# WS2803_7segs_discrete.net
KiCad netlist of a schematic drawn in EAGLE
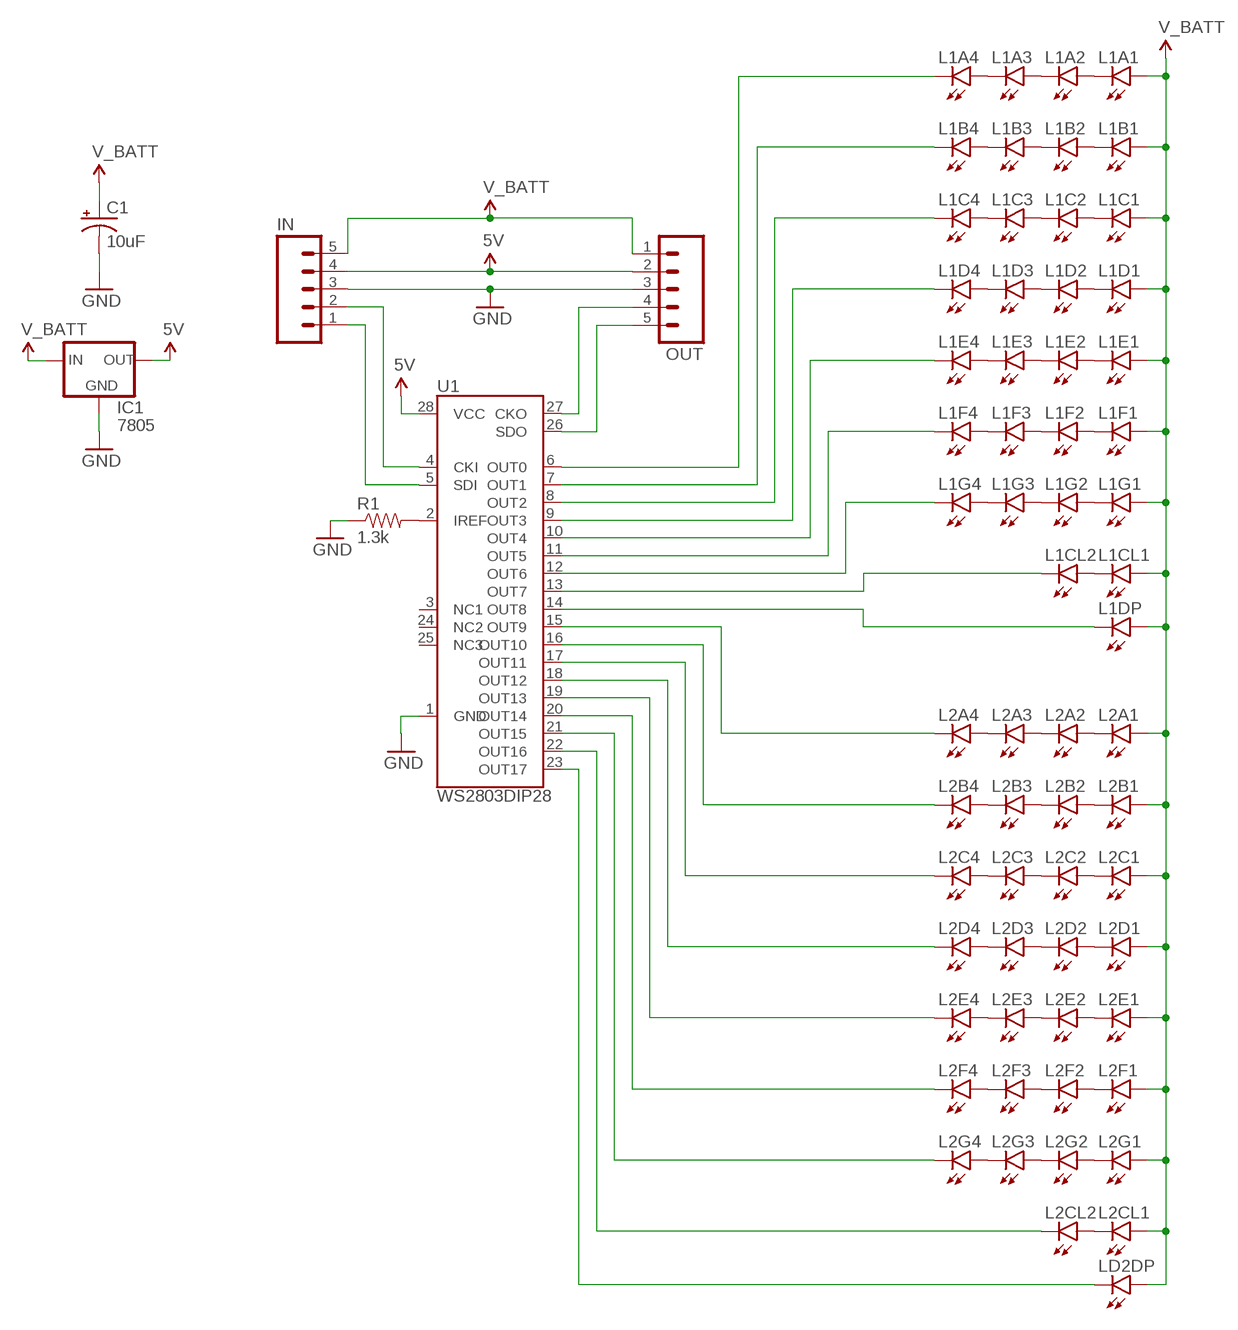
[diagram p0: schematic, sheet 1]

(export (version "E")
  (design (tool "Eeschema 10.0.6"))
  (components
    (comp (ref "C1")
      (value "10uF")
      (footprint "eagle-import:CPOL-RADIAL-10UF-25V")
      (libsource (lib "eagle-import") (part "CAP_POLPTH2"))
    )
    (comp (ref "IC1")
      (value "7805")
      (footprint "eagle-import:TO-92")
      (libsource (lib "eagle-import") (part "V_REG_78XXTO-92_FIXED"))
    )
    (comp (ref "IN")
      (value "M05PTH")
      (footprint "eagle-import:1X05")
      (libsource (lib "eagle-import") (part "M05PTH"))
    )
    (comp (ref "L1A1")
      (value "LED5MM")
      (footprint "eagle-import:LED5MM")
      (libsource (lib "eagle-import") (part "LED5MM"))
    )
    (comp (ref "L1A2")
      (value "LED5MM")
      (footprint "eagle-import:LED5MM")
      (libsource (lib "eagle-import") (part "LED5MM"))
    )
    (comp (ref "L1A3")
      (value "LED5MM")
      (footprint "eagle-import:LED5MM")
      (libsource (lib "eagle-import") (part "LED5MM"))
    )
    (comp (ref "L1A4")
      (value "LED5MM")
      (footprint "eagle-import:LED5MM")
      (libsource (lib "eagle-import") (part "LED5MM"))
    )
    (comp (ref "L1B1")
      (value "LED5MM")
      (footprint "eagle-import:LED5MM")
      (libsource (lib "eagle-import") (part "LED5MM"))
    )
    (comp (ref "L1B2")
      (value "LED5MM")
      (footprint "eagle-import:LED5MM")
      (libsource (lib "eagle-import") (part "LED5MM"))
    )
    (comp (ref "L1B3")
      (value "LED5MM")
      (footprint "eagle-import:LED5MM")
      (libsource (lib "eagle-import") (part "LED5MM"))
    )
    (comp (ref "L1B4")
      (value "LED5MM")
      (footprint "eagle-import:LED5MM")
      (libsource (lib "eagle-import") (part "LED5MM"))
    )
    (comp (ref "L1C1")
      (value "LED5MM")
      (footprint "eagle-import:LED5MM")
      (libsource (lib "eagle-import") (part "LED5MM"))
    )
    (comp (ref "L1C2")
      (value "LED5MM")
      (footprint "eagle-import:LED5MM")
      (libsource (lib "eagle-import") (part "LED5MM"))
    )
    (comp (ref "L1C3")
      (value "LED5MM")
      (footprint "eagle-import:LED5MM")
      (libsource (lib "eagle-import") (part "LED5MM"))
    )
    (comp (ref "L1C4")
      (value "LED5MM")
      (footprint "eagle-import:LED5MM")
      (libsource (lib "eagle-import") (part "LED5MM"))
    )
    (comp (ref "L1CL1")
      (value "LED5MM")
      (footprint "eagle-import:LED5MM")
      (libsource (lib "eagle-import") (part "LED5MM"))
    )
    (comp (ref "L1CL2")
      (value "LED5MM")
      (footprint "eagle-import:LED5MM")
      (libsource (lib "eagle-import") (part "LED5MM"))
    )
    (comp (ref "L1D1")
      (value "LED5MM")
      (footprint "eagle-import:LED5MM")
      (libsource (lib "eagle-import") (part "LED5MM"))
    )
    (comp (ref "L1D2")
      (value "LED5MM")
      (footprint "eagle-import:LED5MM")
      (libsource (lib "eagle-import") (part "LED5MM"))
    )
    (comp (ref "L1D3")
      (value "LED5MM")
      (footprint "eagle-import:LED5MM")
      (libsource (lib "eagle-import") (part "LED5MM"))
    )
    (comp (ref "L1D4")
      (value "LED5MM")
      (footprint "eagle-import:LED5MM")
      (libsource (lib "eagle-import") (part "LED5MM"))
    )
    (comp (ref "L1DP")
      (value "LED5MM")
      (footprint "eagle-import:LED5MM")
      (libsource (lib "eagle-import") (part "LED5MM"))
    )
    (comp (ref "L1E1")
      (value "LED5MM")
      (footprint "eagle-import:LED5MM")
      (libsource (lib "eagle-import") (part "LED5MM"))
    )
    (comp (ref "L1E2")
      (value "LED5MM")
      (footprint "eagle-import:LED5MM")
      (libsource (lib "eagle-import") (part "LED5MM"))
    )
    (comp (ref "L1E3")
      (value "LED5MM")
      (footprint "eagle-import:LED5MM")
      (libsource (lib "eagle-import") (part "LED5MM"))
    )
    (comp (ref "L1E4")
      (value "LED5MM")
      (footprint "eagle-import:LED5MM")
      (libsource (lib "eagle-import") (part "LED5MM"))
    )
    (comp (ref "L1F1")
      (value "LED5MM")
      (footprint "eagle-import:LED5MM")
      (libsource (lib "eagle-import") (part "LED5MM"))
    )
    (comp (ref "L1F2")
      (value "LED5MM")
      (footprint "eagle-import:LED5MM")
      (libsource (lib "eagle-import") (part "LED5MM"))
    )
    (comp (ref "L1F3")
      (value "LED5MM")
      (footprint "eagle-import:LED5MM")
      (libsource (lib "eagle-import") (part "LED5MM"))
    )
    (comp (ref "L1F4")
      (value "LED5MM")
      (footprint "eagle-import:LED5MM")
      (libsource (lib "eagle-import") (part "LED5MM"))
    )
    (comp (ref "L1G1")
      (value "LED5MM")
      (footprint "eagle-import:LED5MM")
      (libsource (lib "eagle-import") (part "LED5MM"))
    )
    (comp (ref "L1G2")
      (value "LED5MM")
      (footprint "eagle-import:LED5MM")
      (libsource (lib "eagle-import") (part "LED5MM"))
    )
    (comp (ref "L1G3")
      (value "LED5MM")
      (footprint "eagle-import:LED5MM")
      (libsource (lib "eagle-import") (part "LED5MM"))
    )
    (comp (ref "L1G4")
      (value "LED5MM")
      (footprint "eagle-import:LED5MM")
      (libsource (lib "eagle-import") (part "LED5MM"))
    )
    (comp (ref "L2A1")
      (value "LED5MM")
      (footprint "eagle-import:LED5MM")
      (libsource (lib "eagle-import") (part "LED5MM"))
    )
    (comp (ref "L2A2")
      (value "LED5MM")
      (footprint "eagle-import:LED5MM")
      (libsource (lib "eagle-import") (part "LED5MM"))
    )
    (comp (ref "L2A3")
      (value "LED5MM")
      (footprint "eagle-import:LED5MM")
      (libsource (lib "eagle-import") (part "LED5MM"))
    )
    (comp (ref "L2A4")
      (value "LED5MM")
      (footprint "eagle-import:LED5MM")
      (libsource (lib "eagle-import") (part "LED5MM"))
    )
    (comp (ref "L2B1")
      (value "LED5MM")
      (footprint "eagle-import:LED5MM")
      (libsource (lib "eagle-import") (part "LED5MM"))
    )
    (comp (ref "L2B2")
      (value "LED5MM")
      (footprint "eagle-import:LED5MM")
      (libsource (lib "eagle-import") (part "LED5MM"))
    )
    (comp (ref "L2B3")
      (value "LED5MM")
      (footprint "eagle-import:LED5MM")
      (libsource (lib "eagle-import") (part "LED5MM"))
    )
    (comp (ref "L2B4")
      (value "LED5MM")
      (footprint "eagle-import:LED5MM")
      (libsource (lib "eagle-import") (part "LED5MM"))
    )
    (comp (ref "L2C1")
      (value "LED5MM")
      (footprint "eagle-import:LED5MM")
      (libsource (lib "eagle-import") (part "LED5MM"))
    )
    (comp (ref "L2C2")
      (value "LED5MM")
      (footprint "eagle-import:LED5MM")
      (libsource (lib "eagle-import") (part "LED5MM"))
    )
    (comp (ref "L2C3")
      (value "LED5MM")
      (footprint "eagle-import:LED5MM")
      (libsource (lib "eagle-import") (part "LED5MM"))
    )
    (comp (ref "L2C4")
      (value "LED5MM")
      (footprint "eagle-import:LED5MM")
      (libsource (lib "eagle-import") (part "LED5MM"))
    )
    (comp (ref "L2CL1")
      (value "LED5MM")
      (footprint "eagle-import:LED5MM")
      (libsource (lib "eagle-import") (part "LED5MM"))
    )
    (comp (ref "L2CL2")
      (value "LED5MM")
      (footprint "eagle-import:LED5MM")
      (libsource (lib "eagle-import") (part "LED5MM"))
    )
    (comp (ref "L2D1")
      (value "LED5MM")
      (footprint "eagle-import:LED5MM")
      (libsource (lib "eagle-import") (part "LED5MM"))
    )
    (comp (ref "L2D2")
      (value "LED5MM")
      (footprint "eagle-import:LED5MM")
      (libsource (lib "eagle-import") (part "LED5MM"))
    )
    (comp (ref "L2D3")
      (value "LED5MM")
      (footprint "eagle-import:LED5MM")
      (libsource (lib "eagle-import") (part "LED5MM"))
    )
    (comp (ref "L2D4")
      (value "LED5MM")
      (footprint "eagle-import:LED5MM")
      (libsource (lib "eagle-import") (part "LED5MM"))
    )
    (comp (ref "L2E1")
      (value "LED5MM")
      (footprint "eagle-import:LED5MM")
      (libsource (lib "eagle-import") (part "LED5MM"))
    )
    (comp (ref "L2E2")
      (value "LED5MM")
      (footprint "eagle-import:LED5MM")
      (libsource (lib "eagle-import") (part "LED5MM"))
    )
    (comp (ref "L2E3")
      (value "LED5MM")
      (footprint "eagle-import:LED5MM")
      (libsource (lib "eagle-import") (part "LED5MM"))
    )
    (comp (ref "L2E4")
      (value "LED5MM")
      (footprint "eagle-import:LED5MM")
      (libsource (lib "eagle-import") (part "LED5MM"))
    )
    (comp (ref "L2F1")
      (value "LED5MM")
      (footprint "eagle-import:LED5MM")
      (libsource (lib "eagle-import") (part "LED5MM"))
    )
    (comp (ref "L2F2")
      (value "LED5MM")
      (footprint "eagle-import:LED5MM")
      (libsource (lib "eagle-import") (part "LED5MM"))
    )
    (comp (ref "L2F3")
      (value "LED5MM")
      (footprint "eagle-import:LED5MM")
      (libsource (lib "eagle-import") (part "LED5MM"))
    )
    (comp (ref "L2F4")
      (value "LED5MM")
      (footprint "eagle-import:LED5MM")
      (libsource (lib "eagle-import") (part "LED5MM"))
    )
    (comp (ref "L2G1")
      (value "LED5MM")
      (footprint "eagle-import:LED5MM")
      (libsource (lib "eagle-import") (part "LED5MM"))
    )
    (comp (ref "L2G2")
      (value "LED5MM")
      (footprint "eagle-import:LED5MM")
      (libsource (lib "eagle-import") (part "LED5MM"))
    )
    (comp (ref "L2G3")
      (value "LED5MM")
      (footprint "eagle-import:LED5MM")
      (libsource (lib "eagle-import") (part "LED5MM"))
    )
    (comp (ref "L2G4")
      (value "LED5MM")
      (footprint "eagle-import:LED5MM")
      (libsource (lib "eagle-import") (part "LED5MM"))
    )
    (comp (ref "LD2DP")
      (value "LED5MM")
      (footprint "eagle-import:LED5MM")
      (libsource (lib "eagle-import") (part "LED5MM"))
    )
    (comp (ref "OUT")
      (value "M05PTH")
      (footprint "eagle-import:1X05")
      (libsource (lib "eagle-import") (part "M05PTH"))
    )
    (comp (ref "R1")
      (value "1.3k")
      (footprint "eagle-import:AXIAL-0.4")
      (libsource (lib "eagle-import") (part "RESISTORPTH-1/4W"))
    )
    (comp (ref "U1")
      (value "WS2803DIP28")
      (footprint "eagle-import:DIP28")
      (libsource (lib "eagle-import") (part "WS2803DIP28"))
    )
  )
  (nets
    (net (code "1") (name "5V") (class "Default")
      (node (ref "IC1") (pin "1") (pinfunction "OUT_1") (pintype "output"))
      (node (ref "IN") (pin "4") (pinfunction "4_4") (pintype "passive"))
      (node (ref "OUT") (pin "2") (pinfunction "2_2") (pintype "passive"))
      (node (ref "U1") (pin "28") (pinfunction "VCC_28") (pintype "bidirectional"))
    )
    (net (code "2") (name "GND") (class "Default")
      (node (ref "C1") (pin "2") (pinfunction "-_2") (pintype "passive"))
      (node (ref "IC1") (pin "2") (pinfunction "GND_2") (pintype "input"))
      (node (ref "IN") (pin "3") (pinfunction "3_3") (pintype "passive"))
      (node (ref "OUT") (pin "3") (pinfunction "3_3") (pintype "passive"))
      (node (ref "R1") (pin "P$1") (pinfunction "1_P$1") (pintype "passive"))
      (node (ref "U1") (pin "1") (pinfunction "GND_1") (pintype "bidirectional"))
    )
    (net (code "3") (name "Net-(L1A1-C)") (class "Default")
      (node (ref "L1A1") (pin "K") (pinfunction "C_K") (pintype "passive"))
      (node (ref "L1A2") (pin "A") (pinfunction "A_A") (pintype "passive"))
    )
    (net (code "4") (name "Net-(L1A2-C)") (class "Default")
      (node (ref "L1A2") (pin "K") (pinfunction "C_K") (pintype "passive"))
      (node (ref "L1A3") (pin "A") (pinfunction "A_A") (pintype "passive"))
    )
    (net (code "5") (name "Net-(L1A3-C)") (class "Default")
      (node (ref "L1A3") (pin "K") (pinfunction "C_K") (pintype "passive"))
      (node (ref "L1A4") (pin "A") (pinfunction "A_A") (pintype "passive"))
    )
    (net (code "6") (name "Net-(L1A4-C)") (class "Default")
      (node (ref "L1A4") (pin "K") (pinfunction "C_K") (pintype "passive"))
      (node (ref "U1") (pin "6") (pinfunction "OUT0_6") (pintype "bidirectional"))
    )
    (net (code "7") (name "Net-(L1B1-C)") (class "Default")
      (node (ref "L1B1") (pin "K") (pinfunction "C_K") (pintype "passive"))
      (node (ref "L1B2") (pin "A") (pinfunction "A_A") (pintype "passive"))
    )
    (net (code "8") (name "Net-(L1B2-C)") (class "Default")
      (node (ref "L1B2") (pin "K") (pinfunction "C_K") (pintype "passive"))
      (node (ref "L1B3") (pin "A") (pinfunction "A_A") (pintype "passive"))
    )
    (net (code "9") (name "Net-(L1B3-C)") (class "Default")
      (node (ref "L1B3") (pin "K") (pinfunction "C_K") (pintype "passive"))
      (node (ref "L1B4") (pin "A") (pinfunction "A_A") (pintype "passive"))
    )
    (net (code "10") (name "Net-(L1B4-C)") (class "Default")
      (node (ref "L1B4") (pin "K") (pinfunction "C_K") (pintype "passive"))
      (node (ref "U1") (pin "7") (pinfunction "OUT1_7") (pintype "bidirectional"))
    )
    (net (code "11") (name "Net-(L1C1-C)") (class "Default")
      (node (ref "L1C1") (pin "K") (pinfunction "C_K") (pintype "passive"))
      (node (ref "L1C2") (pin "A") (pinfunction "A_A") (pintype "passive"))
    )
    (net (code "12") (name "Net-(L1C2-C)") (class "Default")
      (node (ref "L1C2") (pin "K") (pinfunction "C_K") (pintype "passive"))
      (node (ref "L1C3") (pin "A") (pinfunction "A_A") (pintype "passive"))
    )
    (net (code "13") (name "Net-(L1C3-C)") (class "Default")
      (node (ref "L1C3") (pin "K") (pinfunction "C_K") (pintype "passive"))
      (node (ref "L1C4") (pin "A") (pinfunction "A_A") (pintype "passive"))
    )
    (net (code "14") (name "Net-(L1C4-C)") (class "Default")
      (node (ref "L1C4") (pin "K") (pinfunction "C_K") (pintype "passive"))
      (node (ref "U1") (pin "8") (pinfunction "OUT2_8") (pintype "bidirectional"))
    )
    (net (code "15") (name "Net-(L1CL1-C)") (class "Default")
      (node (ref "L1CL1") (pin "K") (pinfunction "C_K") (pintype "passive"))
      (node (ref "L1CL2") (pin "A") (pinfunction "A_A") (pintype "passive"))
    )
    (net (code "16") (name "Net-(L1CL2-C)") (class "Default")
      (node (ref "L1CL2") (pin "K") (pinfunction "C_K") (pintype "passive"))
      (node (ref "U1") (pin "13") (pinfunction "OUT7_13") (pintype "bidirectional"))
    )
    (net (code "17") (name "Net-(L1D1-C)") (class "Default")
      (node (ref "L1D1") (pin "K") (pinfunction "C_K") (pintype "passive"))
      (node (ref "L1D2") (pin "A") (pinfunction "A_A") (pintype "passive"))
    )
    (net (code "18") (name "Net-(L1D2-C)") (class "Default")
      (node (ref "L1D2") (pin "K") (pinfunction "C_K") (pintype "passive"))
      (node (ref "L1D3") (pin "A") (pinfunction "A_A") (pintype "passive"))
    )
    (net (code "19") (name "Net-(L1D3-C)") (class "Default")
      (node (ref "L1D3") (pin "K") (pinfunction "C_K") (pintype "passive"))
      (node (ref "L1D4") (pin "A") (pinfunction "A_A") (pintype "passive"))
    )
    (net (code "20") (name "Net-(L1D4-C)") (class "Default")
      (node (ref "L1D4") (pin "K") (pinfunction "C_K") (pintype "passive"))
      (node (ref "U1") (pin "9") (pinfunction "OUT3_9") (pintype "bidirectional"))
    )
    (net (code "21") (name "Net-(L1DP-C)") (class "Default")
      (node (ref "L1DP") (pin "K") (pinfunction "C_K") (pintype "passive"))
      (node (ref "U1") (pin "14") (pinfunction "OUT8_14") (pintype "bidirectional"))
    )
    (net (code "22") (name "Net-(L1E1-C)") (class "Default")
      (node (ref "L1E1") (pin "K") (pinfunction "C_K") (pintype "passive"))
      (node (ref "L1E2") (pin "A") (pinfunction "A_A") (pintype "passive"))
    )
    (net (code "23") (name "Net-(L1E2-C)") (class "Default")
      (node (ref "L1E2") (pin "K") (pinfunction "C_K") (pintype "passive"))
      (node (ref "L1E3") (pin "A") (pinfunction "A_A") (pintype "passive"))
    )
    (net (code "24") (name "Net-(L1E3-C)") (class "Default")
      (node (ref "L1E3") (pin "K") (pinfunction "C_K") (pintype "passive"))
      (node (ref "L1E4") (pin "A") (pinfunction "A_A") (pintype "passive"))
    )
    (net (code "25") (name "Net-(L1E4-C)") (class "Default")
      (node (ref "L1E4") (pin "K") (pinfunction "C_K") (pintype "passive"))
      (node (ref "U1") (pin "10") (pinfunction "OUT4_10") (pintype "bidirectional"))
    )
    (net (code "26") (name "Net-(L1F1-C)") (class "Default")
      (node (ref "L1F1") (pin "K") (pinfunction "C_K") (pintype "passive"))
      (node (ref "L1F2") (pin "A") (pinfunction "A_A") (pintype "passive"))
    )
    (net (code "27") (name "Net-(L1F2-C)") (class "Default")
      (node (ref "L1F2") (pin "K") (pinfunction "C_K") (pintype "passive"))
      (node (ref "L1F3") (pin "A") (pinfunction "A_A") (pintype "passive"))
    )
    (net (code "28") (name "Net-(L1F3-C)") (class "Default")
      (node (ref "L1F3") (pin "K") (pinfunction "C_K") (pintype "passive"))
      (node (ref "L1F4") (pin "A") (pinfunction "A_A") (pintype "passive"))
    )
    (net (code "29") (name "Net-(L1F4-C)") (class "Default")
      (node (ref "L1F4") (pin "K") (pinfunction "C_K") (pintype "passive"))
      (node (ref "U1") (pin "11") (pinfunction "OUT5_11") (pintype "bidirectional"))
    )
    (net (code "30") (name "Net-(L1G1-C)") (class "Default")
      (node (ref "L1G1") (pin "K") (pinfunction "C_K") (pintype "passive"))
      (node (ref "L1G2") (pin "A") (pinfunction "A_A") (pintype "passive"))
    )
    (net (code "31") (name "Net-(L1G2-C)") (class "Default")
      (node (ref "L1G2") (pin "K") (pinfunction "C_K") (pintype "passive"))
      (node (ref "L1G3") (pin "A") (pinfunction "A_A") (pintype "passive"))
    )
    (net (code "32") (name "Net-(L1G3-C)") (class "Default")
      (node (ref "L1G3") (pin "K") (pinfunction "C_K") (pintype "passive"))
      (node (ref "L1G4") (pin "A") (pinfunction "A_A") (pintype "passive"))
    )
    (net (code "33") (name "Net-(L1G4-C)") (class "Default")
      (node (ref "L1G4") (pin "K") (pinfunction "C_K") (pintype "passive"))
      (node (ref "U1") (pin "12") (pinfunction "OUT6_12") (pintype "bidirectional"))
    )
    (net (code "34") (name "Net-(L2A1-C)") (class "Default")
      (node (ref "L2A1") (pin "K") (pinfunction "C_K") (pintype "passive"))
      (node (ref "L2A2") (pin "A") (pinfunction "A_A") (pintype "passive"))
    )
    (net (code "35") (name "Net-(L2A2-C)") (class "Default")
      (node (ref "L2A2") (pin "K") (pinfunction "C_K") (pintype "passive"))
      (node (ref "L2A3") (pin "A") (pinfunction "A_A") (pintype "passive"))
    )
    (net (code "36") (name "Net-(L2A3-C)") (class "Default")
      (node (ref "L2A3") (pin "K") (pinfunction "C_K") (pintype "passive"))
      (node (ref "L2A4") (pin "A") (pinfunction "A_A") (pintype "passive"))
    )
    (net (code "37") (name "Net-(L2A4-C)") (class "Default")
      (node (ref "L2A4") (pin "K") (pinfunction "C_K") (pintype "passive"))
      (node (ref "U1") (pin "15") (pinfunction "OUT9_15") (pintype "bidirectional"))
    )
    (net (code "38") (name "Net-(L2B1-C)") (class "Default")
      (node (ref "L2B1") (pin "K") (pinfunction "C_K") (pintype "passive"))
      (node (ref "L2B2") (pin "A") (pinfunction "A_A") (pintype "passive"))
    )
    (net (code "39") (name "Net-(L2B2-C)") (class "Default")
      (node (ref "L2B2") (pin "K") (pinfunction "C_K") (pintype "passive"))
      (node (ref "L2B3") (pin "A") (pinfunction "A_A") (pintype "passive"))
    )
    (net (code "40") (name "Net-(L2B3-C)") (class "Default")
      (node (ref "L2B3") (pin "K") (pinfunction "C_K") (pintype "passive"))
      (node (ref "L2B4") (pin "A") (pinfunction "A_A") (pintype "passive"))
    )
    (net (code "41") (name "Net-(L2B4-C)") (class "Default")
      (node (ref "L2B4") (pin "K") (pinfunction "C_K") (pintype "passive"))
      (node (ref "U1") (pin "16") (pinfunction "OUT10_16") (pintype "bidirectional"))
    )
    (net (code "42") (name "Net-(L2C1-C)") (class "Default")
      (node (ref "L2C1") (pin "K") (pinfunction "C_K") (pintype "passive"))
      (node (ref "L2C2") (pin "A") (pinfunction "A_A") (pintype "passive"))
    )
    (net (code "43") (name "Net-(L2C2-C)") (class "Default")
      (node (ref "L2C2") (pin "K") (pinfunction "C_K") (pintype "passive"))
      (node (ref "L2C3") (pin "A") (pinfunction "A_A") (pintype "passive"))
    )
    (net (code "44") (name "Net-(L2C3-C)") (class "Default")
      (node (ref "L2C3") (pin "K") (pinfunction "C_K") (pintype "passive"))
      (node (ref "L2C4") (pin "A") (pinfunction "A_A") (pintype "passive"))
    )
    (net (code "45") (name "Net-(L2C4-C)") (class "Default")
      (node (ref "L2C4") (pin "K") (pinfunction "C_K") (pintype "passive"))
      (node (ref "U1") (pin "17") (pinfunction "OUT11_17") (pintype "bidirectional"))
    )
    (net (code "46") (name "Net-(L2CL1-C)") (class "Default")
      (node (ref "L2CL1") (pin "K") (pinfunction "C_K") (pintype "passive"))
      (node (ref "L2CL2") (pin "A") (pinfunction "A_A") (pintype "passive"))
    )
    (net (code "47") (name "Net-(L2CL2-C)") (class "Default")
      (node (ref "L2CL2") (pin "K") (pinfunction "C_K") (pintype "passive"))
      (node (ref "U1") (pin "22") (pinfunction "OUT16_22") (pintype "bidirectional"))
    )
    (net (code "48") (name "Net-(L2D1-C)") (class "Default")
      (node (ref "L2D1") (pin "K") (pinfunction "C_K") (pintype "passive"))
      (node (ref "L2D2") (pin "A") (pinfunction "A_A") (pintype "passive"))
    )
    (net (code "49") (name "Net-(L2D2-C)") (class "Default")
      (node (ref "L2D2") (pin "K") (pinfunction "C_K") (pintype "passive"))
      (node (ref "L2D3") (pin "A") (pinfunction "A_A") (pintype "passive"))
    )
    (net (code "50") (name "Net-(L2D3-C)") (class "Default")
      (node (ref "L2D3") (pin "K") (pinfunction "C_K") (pintype "passive"))
      (node (ref "L2D4") (pin "A") (pinfunction "A_A") (pintype "passive"))
    )
    (net (code "51") (name "Net-(L2D4-C)") (class "Default")
      (node (ref "L2D4") (pin "K") (pinfunction "C_K") (pintype "passive"))
      (node (ref "U1") (pin "18") (pinfunction "OUT12_18") (pintype "bidirectional"))
    )
    (net (code "52") (name "Net-(L2E1-C)") (class "Default")
      (node (ref "L2E1") (pin "K") (pinfunction "C_K") (pintype "passive"))
      (node (ref "L2E2") (pin "A") (pinfunction "A_A") (pintype "passive"))
    )
    (net (code "53") (name "Net-(L2E2-C)") (class "Default")
      (node (ref "L2E2") (pin "K") (pinfunction "C_K") (pintype "passive"))
      (node (ref "L2E3") (pin "A") (pinfunction "A_A") (pintype "passive"))
    )
    (net (code "54") (name "Net-(L2E3-C)") (class "Default")
      (node (ref "L2E3") (pin "K") (pinfunction "C_K") (pintype "passive"))
      (node (ref "L2E4") (pin "A") (pinfunction "A_A") (pintype "passive"))
    )
    (net (code "55") (name "Net-(L2E4-C)") (class "Default")
      (node (ref "L2E4") (pin "K") (pinfunction "C_K") (pintype "passive"))
      (node (ref "U1") (pin "19") (pinfunction "OUT13_19") (pintype "bidirectional"))
    )
    (net (code "56") (name "Net-(L2F1-C)") (class "Default")
      (node (ref "L2F1") (pin "K") (pinfunction "C_K") (pintype "passive"))
      (node (ref "L2F2") (pin "A") (pinfunction "A_A") (pintype "passive"))
    )
    (net (code "57") (name "Net-(L2F2-C)") (class "Default")
      (node (ref "L2F2") (pin "K") (pinfunction "C_K") (pintype "passive"))
      (node (ref "L2F3") (pin "A") (pinfunction "A_A") (pintype "passive"))
    )
    (net (code "58") (name "Net-(L2F3-C)") (class "Default")
      (node (ref "L2F3") (pin "K") (pinfunction "C_K") (pintype "passive"))
      (node (ref "L2F4") (pin "A") (pinfunction "A_A") (pintype "passive"))
    )
    (net (code "59") (name "Net-(L2F4-C)") (class "Default")
      (node (ref "L2F4") (pin "K") (pinfunction "C_K") (pintype "passive"))
      (node (ref "U1") (pin "20") (pinfunction "OUT14_20") (pintype "bidirectional"))
    )
    (net (code "60") (name "Net-(L2G1-C)") (class "Default")
      (node (ref "L2G1") (pin "K") (pinfunction "C_K") (pintype "passive"))
      (node (ref "L2G2") (pin "A") (pinfunction "A_A") (pintype "passive"))
    )
    (net (code "61") (name "Net-(L2G2-C)") (class "Default")
      (node (ref "L2G2") (pin "K") (pinfunction "C_K") (pintype "passive"))
      (node (ref "L2G3") (pin "A") (pinfunction "A_A") (pintype "passive"))
    )
    (net (code "62") (name "Net-(L2G3-C)") (class "Default")
      (node (ref "L2G3") (pin "K") (pinfunction "C_K") (pintype "passive"))
      (node (ref "L2G4") (pin "A") (pinfunction "A_A") (pintype "passive"))
    )
    (net (code "63") (name "Net-(L2G4-C)") (class "Default")
      (node (ref "L2G4") (pin "K") (pinfunction "C_K") (pintype "passive"))
      (node (ref "U1") (pin "21") (pinfunction "OUT15_21") (pintype "bidirectional"))
    )
    (net (code "64") (name "Net-(LD2DP-C)") (class "Default")
      (node (ref "LD2DP") (pin "K") (pinfunction "C_K") (pintype "passive"))
      (node (ref "U1") (pin "23") (pinfunction "OUT17_23") (pintype "bidirectional"))
    )
    (net (code "65") (name "Net-(R1-2)") (class "Default")
      (node (ref "R1") (pin "P$2") (pinfunction "2_P$2") (pintype "passive"))
      (node (ref "U1") (pin "2") (pinfunction "IREF_2") (pintype "bidirectional"))
    )
    (net (code "66") (name "Net-(U1-CKI)") (class "Default")
      (node (ref "IN") (pin "2") (pinfunction "2_2") (pintype "passive"))
      (node (ref "U1") (pin "4") (pinfunction "CKI_4") (pintype "bidirectional"))
    )
    (net (code "67") (name "Net-(U1-CKO)") (class "Default")
      (node (ref "OUT") (pin "4") (pinfunction "4_4") (pintype "passive"))
      (node (ref "U1") (pin "27") (pinfunction "CKO_27") (pintype "bidirectional"))
    )
    (net (code "68") (name "Net-(U1-SDI)") (class "Default")
      (node (ref "IN") (pin "1") (pinfunction "1_1") (pintype "passive"))
      (node (ref "U1") (pin "5") (pinfunction "SDI_5") (pintype "bidirectional"))
    )
    (net (code "69") (name "Net-(U1-SDO)") (class "Default")
      (node (ref "OUT") (pin "5") (pinfunction "5_5") (pintype "passive"))
      (node (ref "U1") (pin "26") (pinfunction "SDO_26") (pintype "bidirectional"))
    )
    (net (code "70") (name "V_BATT") (class "Default")
      (node (ref "C1") (pin "1") (pinfunction "+_1") (pintype "passive"))
      (node (ref "IC1") (pin "3") (pinfunction "IN_3") (pintype "input"))
      (node (ref "IN") (pin "5") (pinfunction "5_5") (pintype "passive"))
      (node (ref "L1A1") (pin "A") (pinfunction "A_A") (pintype "passive"))
      (node (ref "L1B1") (pin "A") (pinfunction "A_A") (pintype "passive"))
      (node (ref "L1C1") (pin "A") (pinfunction "A_A") (pintype "passive"))
      (node (ref "L1CL1") (pin "A") (pinfunction "A_A") (pintype "passive"))
      (node (ref "L1D1") (pin "A") (pinfunction "A_A") (pintype "passive"))
      (node (ref "L1DP") (pin "A") (pinfunction "A_A") (pintype "passive"))
      (node (ref "L1E1") (pin "A") (pinfunction "A_A") (pintype "passive"))
      (node (ref "L1F1") (pin "A") (pinfunction "A_A") (pintype "passive"))
      (node (ref "L1G1") (pin "A") (pinfunction "A_A") (pintype "passive"))
      (node (ref "L2A1") (pin "A") (pinfunction "A_A") (pintype "passive"))
      (node (ref "L2B1") (pin "A") (pinfunction "A_A") (pintype "passive"))
      (node (ref "L2C1") (pin "A") (pinfunction "A_A") (pintype "passive"))
      (node (ref "L2CL1") (pin "A") (pinfunction "A_A") (pintype "passive"))
      (node (ref "L2D1") (pin "A") (pinfunction "A_A") (pintype "passive"))
      (node (ref "L2E1") (pin "A") (pinfunction "A_A") (pintype "passive"))
      (node (ref "L2F1") (pin "A") (pinfunction "A_A") (pintype "passive"))
      (node (ref "L2G1") (pin "A") (pinfunction "A_A") (pintype "passive"))
      (node (ref "LD2DP") (pin "A") (pinfunction "A_A") (pintype "passive"))
      (node (ref "OUT") (pin "1") (pinfunction "1_1") (pintype "passive"))
    )
    (net (code "71") (name "unconnected-(U1-NC1-Pad3)") (class "Default")
      (node (ref "U1") (pin "3") (pinfunction "NC1_3") (pintype "bidirectional"))
    )
    (net (code "72") (name "unconnected-(U1-NC2-Pad24)") (class "Default")
      (node (ref "U1") (pin "24") (pinfunction "NC2_24") (pintype "bidirectional"))
    )
    (net (code "73") (name "unconnected-(U1-NC3-Pad25)") (class "Default")
      (node (ref "U1") (pin "25") (pinfunction "NC3_25") (pintype "bidirectional"))
    )
  )
)
